# MacroPad.net
KiCad netlist of a schematic drawn in EAGLE
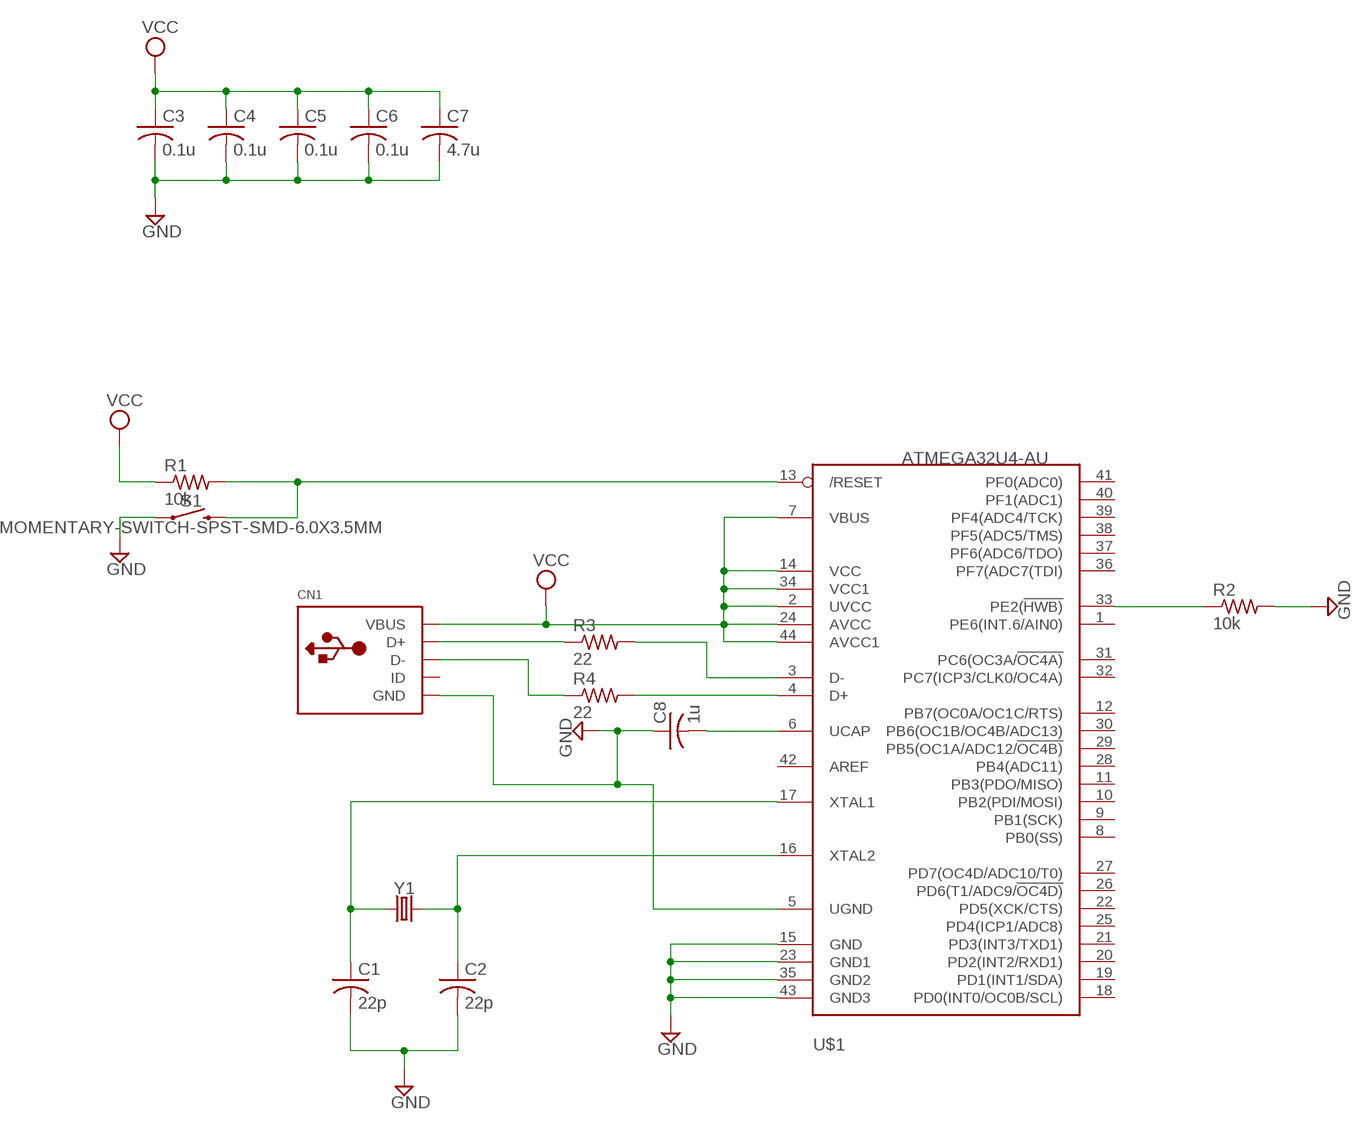
[diagram p0: schematic, sheet 1]

(export (version "E")
  (design (tool "Eeschema 10.0.6"))
  (components
    (comp (ref "C1")
      (value "22p")
      (footprint "eagle-import:C0805")
      (libsource (lib "eagle-import") (part "C-USC0805"))
    )
    (comp (ref "C2")
      (value "22p")
      (footprint "eagle-import:C0805")
      (libsource (lib "eagle-import") (part "C-USC0805"))
    )
    (comp (ref "C3")
      (value "0.1u")
      (footprint "eagle-import:C0805")
      (libsource (lib "eagle-import") (part "C-USC0805"))
    )
    (comp (ref "C4")
      (value "0.1u")
      (footprint "eagle-import:C0805")
      (libsource (lib "eagle-import") (part "C-USC0805"))
    )
    (comp (ref "C5")
      (value "0.1u")
      (footprint "eagle-import:C0805")
      (libsource (lib "eagle-import") (part "C-USC0805"))
    )
    (comp (ref "C6")
      (value "0.1u")
      (footprint "eagle-import:C0805")
      (libsource (lib "eagle-import") (part "C-USC0805"))
    )
    (comp (ref "C7")
      (value "4.7u")
      (footprint "eagle-import:C0805")
      (libsource (lib "eagle-import") (part "C-USC0805"))
    )
    (comp (ref "C8")
      (value "1u")
      (footprint "eagle-import:C0805")
      (libsource (lib "eagle-import") (part "C-USC0805"))
    )
    (comp (ref "CN1")
      (value "USBMOLEX")
      (footprint "eagle-import:USB-MINIB-THM-MOLEX")
      (libsource (lib "eagle-import") (part "USBMOLEX"))
    )
    (comp (ref "R1")
      (value "10k")
      (footprint "eagle-import:R0805")
      (fields (field (name "SPICEPREFIX") "R"))
      (libsource (lib "eagle-import") (part "R-US_R0805"))
    )
    (comp (ref "R2")
      (value "10k")
      (footprint "eagle-import:R0805")
      (libsource (lib "eagle-import") (part "R-US_R0805"))
    )
    (comp (ref "R3")
      (value "22")
      (footprint "eagle-import:R0805")
      (fields (field (name "SPICEPREFIX") "R"))
      (libsource (lib "eagle-import") (part "R-US_R0805"))
    )
    (comp (ref "R4")
      (value "22")
      (footprint "eagle-import:R0805")
      (fields (field (name "SPICEPREFIX") "R"))
      (libsource (lib "eagle-import") (part "R-US_R0805"))
    )
    (comp (ref "S1")
      (value "MOMENTARY-SWITCH-SPST-SMD-6.0X3.5MM")
      (footprint "eagle-import:TACTILE_SWITCH_SMD_6.0X3.5MM")
      (fields (field (name "SPICEPREFIX") "B"))
      (libsource (lib "eagle-import") (part "MOMENTARY-SWITCH-SPST-SMD-6.0X3.5MM"))
    )
    (comp (ref "U$1")
      (value "ATMEGA32U4-AU")
      (footprint "eagle-import:TQFP44")
      (libsource (lib "eagle-import") (part "ATMEGA32U4-AU"))
    )
    (comp (ref "Y1")
      (value "CRYSTALSMD-5X3.2-4PAD")
      (footprint "eagle-import:CRYSTAL-SMD-5X3.2-4PAD")
      (libsource (lib "eagle-import") (part "CRYSTALSMD-5X3.2-4PAD"))
    )
  )
  (nets
    (net (code "1") (name "GND") (class "Default")
      (node (ref "C1") (pin "2") (pinfunction "2_2") (pintype "passive"))
      (node (ref "C2") (pin "2") (pinfunction "2_2") (pintype "passive"))
      (node (ref "C3") (pin "2") (pinfunction "2_2") (pintype "passive"))
      (node (ref "C4") (pin "2") (pinfunction "2_2") (pintype "passive"))
      (node (ref "C5") (pin "2") (pinfunction "2_2") (pintype "passive"))
      (node (ref "C6") (pin "2") (pinfunction "2_2") (pintype "passive"))
      (node (ref "C7") (pin "2") (pinfunction "2_2") (pintype "passive"))
      (node (ref "C8") (pin "1") (pinfunction "1_1") (pintype "passive"))
      (node (ref "CN1") (pin "GND") (pinfunction "GND_GND") (pintype "power_in"))
      (node (ref "R2") (pin "2") (pinfunction "2_2") (pintype "passive"))
      (node (ref "S1") (pin "1") (pinfunction "1_1") (pintype "passive"))
      (node (ref "U$1") (pin "15") (pinfunction "GND_15") (pintype "bidirectional"))
      (node (ref "U$1") (pin "23") (pinfunction "GND1_23") (pintype "bidirectional"))
      (node (ref "U$1") (pin "35") (pinfunction "GND2_35") (pintype "bidirectional"))
      (node (ref "U$1") (pin "43") (pinfunction "GND3_43") (pintype "bidirectional"))
      (node (ref "U$1") (pin "5") (pinfunction "UGND_5") (pintype "bidirectional"))
    )
    (net (code "2") (name "Net-(CN1-PadD+)") (class "Default")
      (node (ref "CN1") (pin "D+") (pinfunction "D+_D+") (pintype "bidirectional"))
      (node (ref "R3") (pin "1") (pinfunction "1_1") (pintype "passive"))
    )
    (net (code "3") (name "Net-(CN1-PadD-)") (class "Default")
      (node (ref "CN1") (pin "D-") (pinfunction "D-_D-") (pintype "bidirectional"))
      (node (ref "R4") (pin "1") (pinfunction "1_1") (pintype "passive"))
    )
    (net (code "4") (name "Net-(U$1-D+)") (class "Default")
      (node (ref "R4") (pin "2") (pinfunction "2_2") (pintype "passive"))
      (node (ref "U$1") (pin "4") (pinfunction "D+_4") (pintype "bidirectional"))
    )
    (net (code "5") (name "Net-(U$1-D-)") (class "Default")
      (node (ref "R3") (pin "2") (pinfunction "2_2") (pintype "passive"))
      (node (ref "U$1") (pin "3") (pinfunction "D-_3") (pintype "bidirectional"))
    )
    (net (code "6") (name "Net-(U$1-PE2(~{HWB}))") (class "Default")
      (node (ref "R2") (pin "1") (pinfunction "1_1") (pintype "passive"))
      (node (ref "U$1") (pin "33") (pinfunction "PE2(~{HWB})_33") (pintype "bidirectional"))
    )
    (net (code "7") (name "Net-(U$1-UCAP)") (class "Default")
      (node (ref "C8") (pin "2") (pinfunction "2_2") (pintype "passive"))
      (node (ref "U$1") (pin "6") (pinfunction "UCAP_6") (pintype "bidirectional"))
    )
    (net (code "8") (name "Net-(U$1-XTAL1)") (class "Default")
      (node (ref "C1") (pin "1") (pinfunction "1_1") (pintype "passive"))
      (node (ref "U$1") (pin "17") (pinfunction "XTAL1_17") (pintype "bidirectional"))
      (node (ref "Y1") (pin "1") (pinfunction "1_1") (pintype "passive"))
    )
    (net (code "9") (name "Net-(U$1-XTAL2)") (class "Default")
      (node (ref "C2") (pin "1") (pinfunction "1_1") (pintype "passive"))
      (node (ref "U$1") (pin "16") (pinfunction "XTAL2_16") (pintype "bidirectional"))
      (node (ref "Y1") (pin "3") (pinfunction "2_3") (pintype "passive"))
    )
    (net (code "10") (name "Net-(U$1-{slash}RESET)") (class "Default")
      (node (ref "R1") (pin "2") (pinfunction "2_2") (pintype "passive"))
      (node (ref "S1") (pin "2") (pinfunction "2_2") (pintype "passive"))
      (node (ref "U$1") (pin "13") (pinfunction "/RESET_13") (pintype "bidirectional"))
    )
    (net (code "11") (name "VCC") (class "Default")
      (node (ref "C3") (pin "1") (pinfunction "1_1") (pintype "passive"))
      (node (ref "C4") (pin "1") (pinfunction "1_1") (pintype "passive"))
      (node (ref "C5") (pin "1") (pinfunction "1_1") (pintype "passive"))
      (node (ref "C6") (pin "1") (pinfunction "1_1") (pintype "passive"))
      (node (ref "C7") (pin "1") (pinfunction "1_1") (pintype "passive"))
      (node (ref "CN1") (pin "VBUS") (pinfunction "VBUS_VBUS") (pintype "power_in"))
      (node (ref "R1") (pin "1") (pinfunction "1_1") (pintype "passive"))
      (node (ref "U$1") (pin "14") (pinfunction "VCC_14") (pintype "bidirectional"))
      (node (ref "U$1") (pin "2") (pinfunction "UVCC_2") (pintype "bidirectional"))
      (node (ref "U$1") (pin "24") (pinfunction "AVCC_24") (pintype "bidirectional"))
      (node (ref "U$1") (pin "34") (pinfunction "VCC1_34") (pintype "bidirectional"))
      (node (ref "U$1") (pin "44") (pinfunction "AVCC1_44") (pintype "bidirectional"))
      (node (ref "U$1") (pin "7") (pinfunction "VBUS_7") (pintype "bidirectional"))
    )
    (net (code "12") (name "unconnected-(CN1-PadID)") (class "Default")
      (node (ref "CN1") (pin "ID") (pinfunction "ID_ID") (pintype "bidirectional"))
    )
    (net (code "13") (name "unconnected-(U$1-AREF-Pad42)") (class "Default")
      (node (ref "U$1") (pin "42") (pinfunction "AREF_42") (pintype "bidirectional"))
    )
    (net (code "14") (name "unconnected-(U$1-PB0(SS)-Pad8)") (class "Default")
      (node (ref "U$1") (pin "8") (pinfunction "PB0(SS)_8") (pintype "bidirectional"))
    )
    (net (code "15") (name "unconnected-(U$1-PB1(SCK)-Pad9)") (class "Default")
      (node (ref "U$1") (pin "9") (pinfunction "PB1(SCK)_9") (pintype "bidirectional"))
    )
    (net (code "16") (name "unconnected-(U$1-PB2(PDI{slash}MOSI)-Pad10)") (class "Default")
      (node (ref "U$1") (pin "10") (pinfunction "PB2(PDI/MOSI)_10") (pintype "bidirectional"))
    )
    (net (code "17") (name "unconnected-(U$1-PB3(PDO{slash}MISO)-Pad11)") (class "Default")
      (node (ref "U$1") (pin "11") (pinfunction "PB3(PDO/MISO)_11") (pintype "bidirectional"))
    )
    (net (code "18") (name "unconnected-(U$1-PB4(ADC11)-Pad28)") (class "Default")
      (node (ref "U$1") (pin "28") (pinfunction "PB4(ADC11)_28") (pintype "bidirectional"))
    )
    (net (code "19") (name "unconnected-(U$1-PB5(OC1A{slash}ADC12{slash}~{OC4B})-Pad29)") (class "Default")
      (node (ref "U$1") (pin "29") (pinfunction "PB5(OC1A/ADC12/~{OC4B})_29") (pintype "bidirectional"))
    )
    (net (code "20") (name "unconnected-(U$1-PB6(OC1B{slash}OC4B{slash}ADC13)-Pad30)") (class "Default")
      (node (ref "U$1") (pin "30") (pinfunction "PB6(OC1B/OC4B/ADC13)_30") (pintype "bidirectional"))
    )
    (net (code "21") (name "unconnected-(U$1-PB7(OC0A{slash}OC1C{slash}RTS)-Pad12)") (class "Default")
      (node (ref "U$1") (pin "12") (pinfunction "PB7(OC0A/OC1C/RTS)_12") (pintype "bidirectional"))
    )
    (net (code "22") (name "unconnected-(U$1-PC6(OC3A{slash}~{OC4A})-Pad31)") (class "Default")
      (node (ref "U$1") (pin "31") (pinfunction "PC6(OC3A/~{OC4A})_31") (pintype "bidirectional"))
    )
    (net (code "23") (name "unconnected-(U$1-PC7(ICP3{slash}CLK0{slash}OC4A)-Pad32)") (class "Default")
      (node (ref "U$1") (pin "32") (pinfunction "PC7(ICP3/CLK0/OC4A)_32") (pintype "bidirectional"))
    )
    (net (code "24") (name "unconnected-(U$1-PD0(INT0{slash}OC0B{slash}SCL)-Pad18)") (class "Default")
      (node (ref "U$1") (pin "18") (pinfunction "PD0(INT0/OC0B/SCL)_18") (pintype "bidirectional"))
    )
    (net (code "25") (name "unconnected-(U$1-PD1(INT1{slash}SDA)-Pad19)") (class "Default")
      (node (ref "U$1") (pin "19") (pinfunction "PD1(INT1/SDA)_19") (pintype "bidirectional"))
    )
    (net (code "26") (name "unconnected-(U$1-PD2(INT2{slash}RXD1)-Pad20)") (class "Default")
      (node (ref "U$1") (pin "20") (pinfunction "PD2(INT2/RXD1)_20") (pintype "bidirectional"))
    )
    (net (code "27") (name "unconnected-(U$1-PD3(INT3{slash}TXD1)-Pad21)") (class "Default")
      (node (ref "U$1") (pin "21") (pinfunction "PD3(INT3/TXD1)_21") (pintype "bidirectional"))
    )
    (net (code "28") (name "unconnected-(U$1-PD4(ICP1{slash}ADC8)-Pad25)") (class "Default")
      (node (ref "U$1") (pin "25") (pinfunction "PD4(ICP1/ADC8)_25") (pintype "bidirectional"))
    )
    (net (code "29") (name "unconnected-(U$1-PD5(XCK{slash}CTS)-Pad22)") (class "Default")
      (node (ref "U$1") (pin "22") (pinfunction "PD5(XCK/CTS)_22") (pintype "bidirectional"))
    )
    (net (code "30") (name "unconnected-(U$1-PD6(T1{slash}ADC9{slash}~{OC4D})-Pad26)") (class "Default")
      (node (ref "U$1") (pin "26") (pinfunction "PD6(T1/ADC9/~{OC4D})_26") (pintype "bidirectional"))
    )
    (net (code "31") (name "unconnected-(U$1-PD7(OC4D{slash}ADC10{slash}T0)-Pad27)") (class "Default")
      (node (ref "U$1") (pin "27") (pinfunction "PD7(OC4D/ADC10/T0)_27") (pintype "bidirectional"))
    )
    (net (code "32") (name "unconnected-(U$1-PE6(INT.6{slash}AIN0)-Pad1)") (class "Default")
      (node (ref "U$1") (pin "1") (pinfunction "PE6(INT.6/AIN0)_1") (pintype "bidirectional"))
    )
    (net (code "33") (name "unconnected-(U$1-PF0(ADC0)-Pad41)") (class "Default")
      (node (ref "U$1") (pin "41") (pinfunction "PF0(ADC0)_41") (pintype "bidirectional"))
    )
    (net (code "34") (name "unconnected-(U$1-PF1(ADC1)-Pad40)") (class "Default")
      (node (ref "U$1") (pin "40") (pinfunction "PF1(ADC1)_40") (pintype "bidirectional"))
    )
    (net (code "35") (name "unconnected-(U$1-PF4(ADC4{slash}TCK)-Pad39)") (class "Default")
      (node (ref "U$1") (pin "39") (pinfunction "PF4(ADC4/TCK)_39") (pintype "bidirectional"))
    )
    (net (code "36") (name "unconnected-(U$1-PF5(ADC5{slash}TMS)-Pad38)") (class "Default")
      (node (ref "U$1") (pin "38") (pinfunction "PF5(ADC5/TMS)_38") (pintype "bidirectional"))
    )
    (net (code "37") (name "unconnected-(U$1-PF6(ADC6{slash}TDO)-Pad37)") (class "Default")
      (node (ref "U$1") (pin "37") (pinfunction "PF6(ADC6/TDO)_37") (pintype "bidirectional"))
    )
    (net (code "38") (name "unconnected-(U$1-PF7(ADC7(TDI)-Pad36)") (class "Default")
      (node (ref "U$1") (pin "36") (pinfunction "PF7(ADC7(TDI)_36") (pintype "bidirectional"))
    )
  )
)
